# PHENIKA.net
KiCad netlist of a schematic drawn in Altium Designer
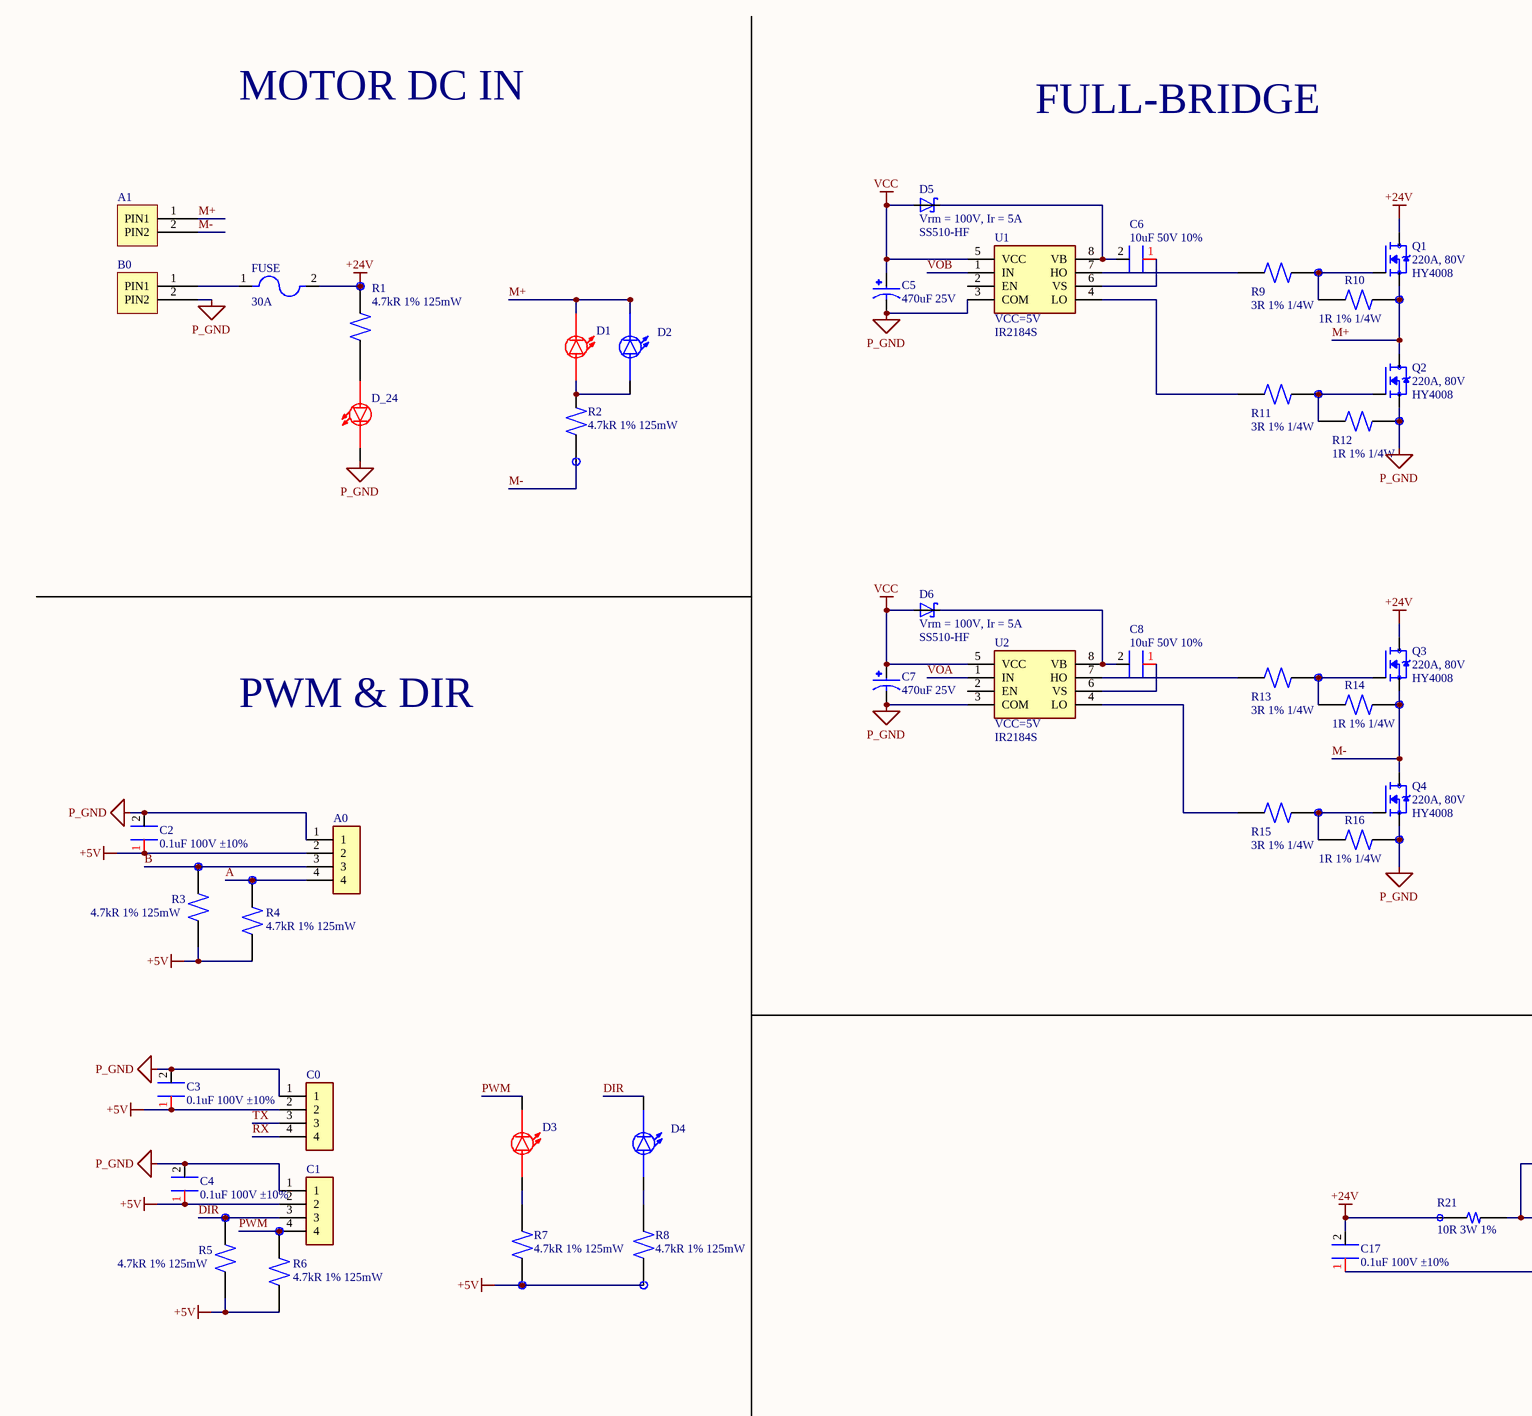
[diagram p0: PHENIKA.SchDoc, left]
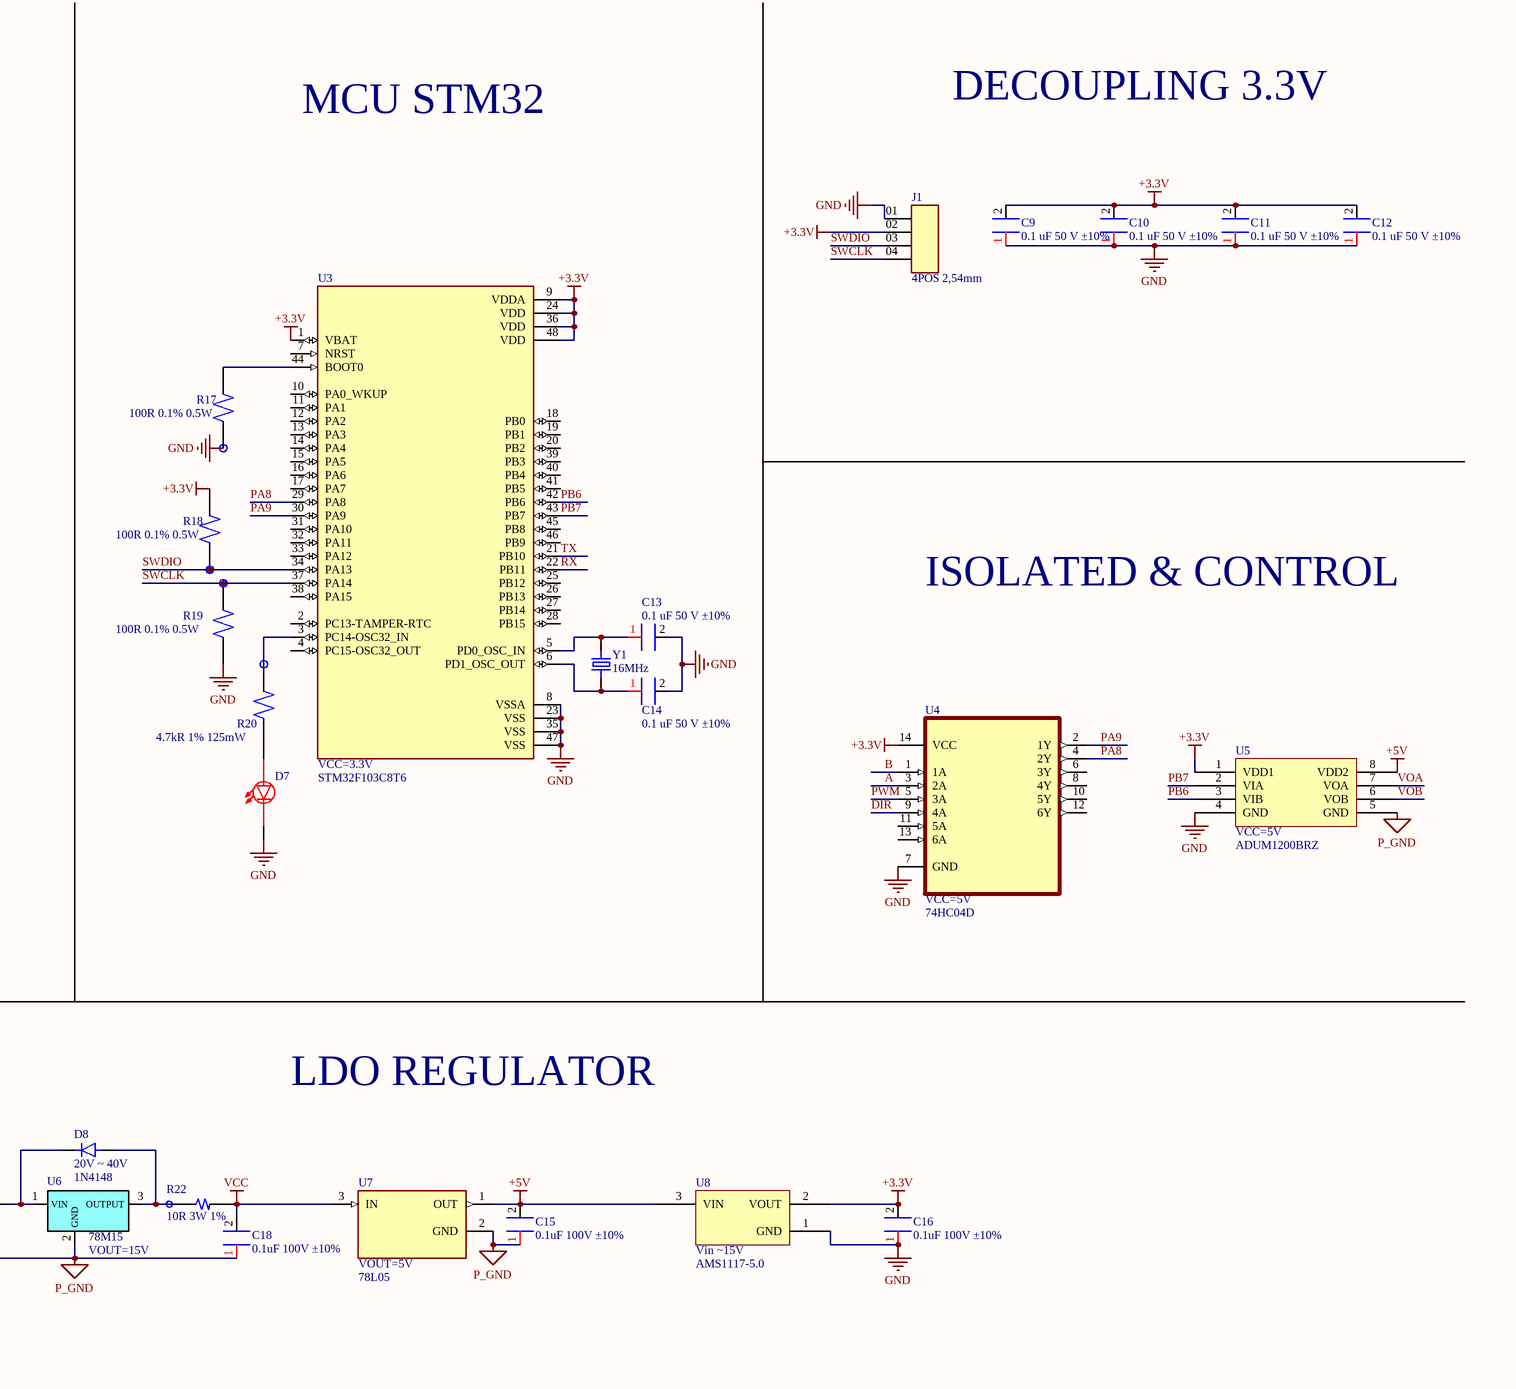
[diagram p1: PHENIKA.SchDoc, right]

(export (version "E")
  (design (tool "Eeschema 10.0.6"))
  (components
    (comp (ref "A0")
      (value "4PIN 2.5 mm")
      (footprint "HEADER-4POS_CURVED_2.54mm")
      (description "Connector Header Through Hole, Right Angle 4 position 0.079\" (2.00mm)")
      (fields
        (field (name "MANUFACTURER PART NUMBER") "S4B-PH-K-S")
        (field (name "MANUFACTURER") "JST Sales America Inc.")
      )
      (libsource (lib "MINH_REUS_LIB") (part "HEADER _4PIN;TH CURVED;2.54mm"))
    )
    (comp (ref "A1")
      (value "2PIN 2.54mm")
      (footprint "HEADER-CONN_2POS_2.54mm")
      (description "CONN HEADER VERT 2POS 2.5MM")
      (fields
        (field (name "MANUFACTURER PART NUMBER") "JST Sales America Inc.")
        (field (name "MANUFACTURER") "B2B-XH-A")
      )
      (libsource (lib "MINH_REUS_LIB") (part "HEADER 2 PIN;TH;2.54mm"))
    )
    (comp (ref "B0")
      (value "2PIN 2.54mm")
      (footprint "HEADER-CONN_2POS_2.54mm")
      (description "CONN HEADER VERT 2POS 2.5MM")
      (fields
        (field (name "MANUFACTURER PART NUMBER") "JST Sales America Inc.")
        (field (name "MANUFACTURER") "B2B-XH-A")
      )
      (libsource (lib "MINH_REUS_LIB") (part "HEADER 2 PIN;TH;2.54mm"))
    )
    (comp (ref "C0")
      (value "4PIN 2.5 mm")
      (footprint "HEADER-4POS_CURVED_2.54mm")
      (description "Connector Header Through Hole, Right Angle 4 position 0.079\" (2.00mm)")
      (fields
        (field (name "MANUFACTURER PART NUMBER") "S4B-PH-K-S")
        (field (name "MANUFACTURER") "JST Sales America Inc.")
      )
      (libsource (lib "MINH_REUS_LIB") (part "HEADER _4PIN;TH CURVED;2.54mm"))
    )
    (comp (ref "C1")
      (value "4PIN 2.5 mm")
      (footprint "HEADER-4POS_CURVED_2.54mm")
      (description "Connector Header Through Hole, Right Angle 4 position 0.079\" (2.00mm)")
      (fields
        (field (name "MANUFACTURER PART NUMBER") "S4B-PH-K-S")
        (field (name "MANUFACTURER") "JST Sales America Inc.")
      )
      (libsource (lib "MINH_REUS_LIB") (part "HEADER _4PIN;TH CURVED;2.54mm"))
    )
    (comp (ref "C2")
      (value "0.1uF 100V ±10%")
      (footprint "CAP-CER_1206 3.2x1.6x0.5mm SMD")
      (description "Multilayer Ceramic Capacitor, 0.1 uF, 100 V, ± 10%, X7R, 1206 [3216 Metric]")
      (fields
        (field (name "MANUFACTURER") "Yageo")
        (field (name "MANUFACTURER PART NUMBER") "CC1206KKX7R0BB104")
      )
      (libsource (lib "MINH_REUS_LIB") (part "CAP_CER; SMD; 0.1uF 100V ±10%;1206;"))
    )
    (comp (ref "C3")
      (value "0.1uF 100V ±10%")
      (footprint "CAP-CER_1206 3.2x1.6x0.5mm SMD")
      (description "Multilayer Ceramic Capacitor, 0.1 uF, 100 V, ± 10%, X7R, 1206 [3216 Metric]")
      (fields
        (field (name "MANUFACTURER") "Yageo")
        (field (name "MANUFACTURER PART NUMBER") "CC1206KKX7R0BB104")
      )
      (libsource (lib "MINH_REUS_LIB") (part "CAP_CER; SMD; 0.1uF 100V ±10%;1206;"))
    )
    (comp (ref "C4")
      (value "0.1uF 100V ±10%")
      (footprint "CAP-CER_1206 3.2x1.6x0.5mm SMD")
      (description "Multilayer Ceramic Capacitor, 0.1 uF, 100 V, ± 10%, X7R, 1206 [3216 Metric]")
      (fields
        (field (name "MANUFACTURER") "Yageo")
        (field (name "MANUFACTURER PART NUMBER") "CC1206KKX7R0BB104")
      )
      (libsource (lib "MINH_REUS_LIB") (part "CAP_CER; SMD; 0.1uF 100V ±10%;1206;"))
    )
    (comp (ref "C5")
      (value "470uF 25V")
      (footprint "CAP-POLARIZED TH 25V 3x5mm")
      (description "CAP_ALUM;TH;EEU-TP1E471LB;470礔 25V Aluminum Electrolytic Capacitors Radial, Can 2000 Hrs @ 125掳C")
      (fields
        (field (name "MANUFACTURER") "Panasonic")
        (field (name "MANUFACTURER PART NUMBER") "EEUTP1E471LB")
      )
      (libsource (lib "MINH_REUS_LIB") (part "CAP_ALUM;TH;470µF 25V"))
    )
    (comp (ref "C6")
      (value "10uF 50V 10%")
      (footprint "CAP-CER_0805 SMD 2.01x1.25mm")
      (description "Ceramic Capacitor, Multilayer, Ceramic, 50V, 10% +Tol, 10% -Tol, X5R, 10uF, Surface Mount, 0805")
      (fields
        (field (name "MANUFACTURER") "Murata")
        (field (name "MANUFACTURER PART NUMBER") "GRM21BR61H106KE43K")
      )
      (libsource (lib "MINH_REUS_LIB") (part "CAP_CER;10uF 50V 10%;SMD;0805"))
    )
    (comp (ref "C7")
      (value "470uF 25V")
      (footprint "CAP-POLARIZED TH 25V 3x5mm")
      (description "CAP_ALUM;TH;EEU-TP1E471LB;470礔 25V Aluminum Electrolytic Capacitors Radial, Can 2000 Hrs @ 125掳C")
      (fields
        (field (name "MANUFACTURER") "Panasonic")
        (field (name "MANUFACTURER PART NUMBER") "EEUTP1E471LB")
      )
      (libsource (lib "MINH_REUS_LIB") (part "CAP_ALUM;TH;470µF 25V"))
    )
    (comp (ref "C8")
      (value "10uF 50V 10%")
      (footprint "CAP-CER_0805 SMD 2.01x1.25mm")
      (description "Ceramic Capacitor, Multilayer, Ceramic, 50V, 10% +Tol, 10% -Tol, X5R, 10uF, Surface Mount, 0805")
      (fields
        (field (name "MANUFACTURER") "Murata")
        (field (name "MANUFACTURER PART NUMBER") "GRM21BR61H106KE43K")
      )
      (libsource (lib "MINH_REUS_LIB") (part "CAP_CER;10uF 50V 10%;SMD;0805"))
    )
    (comp (ref "C9")
      (value "0.1 uF 50 V ±10%")
      (footprint "CAP-CER_0805 SMD 2.01x1.25mm")
      (description "Multilayer Ceramic Capacitor, 0.1 uF, 50 V, ± 10%, X7R, 0805 [2012 Metric]")
      (fields
        (field (name "MANUFACTURER") "Kyocera AVX")
        (field (name "MANUFACTURER PART NUMBER") "08055C104K4T4A")
      )
      (libsource (lib "MINH_REUS_LIB") (part "CAP_CER; SMD; 0.1uF 50V ±10%;0805;"))
    )
    (comp (ref "C10")
      (value "0.1 uF 50 V ±10%")
      (footprint "CAP-CER_0805 SMD 2.01x1.25mm")
      (description "Multilayer Ceramic Capacitor, 0.1 uF, 50 V, ± 10%, X7R, 0805 [2012 Metric]")
      (fields
        (field (name "MANUFACTURER") "Kyocera AVX")
        (field (name "MANUFACTURER PART NUMBER") "08055C104K4T4A")
      )
      (libsource (lib "MINH_REUS_LIB") (part "CAP_CER; SMD; 0.1uF 50V ±10%;0805;"))
    )
    (comp (ref "C11")
      (value "0.1 uF 50 V ±10%")
      (footprint "CAP-CER_0805 SMD 2.01x1.25mm")
      (description "Multilayer Ceramic Capacitor, 0.1 uF, 50 V, ± 10%, X7R, 0805 [2012 Metric]")
      (fields
        (field (name "MANUFACTURER") "Kyocera AVX")
        (field (name "MANUFACTURER PART NUMBER") "08055C104K4T4A")
      )
      (libsource (lib "MINH_REUS_LIB") (part "CAP_CER; SMD; 0.1uF 50V ±10%;0805;"))
    )
    (comp (ref "C12")
      (value "0.1 uF 50 V ±10%")
      (footprint "CAP-CER_0805 SMD 2.01x1.25mm")
      (description "Multilayer Ceramic Capacitor, 0.1 uF, 50 V, ± 10%, X7R, 0805 [2012 Metric]")
      (fields
        (field (name "MANUFACTURER") "Kyocera AVX")
        (field (name "MANUFACTURER PART NUMBER") "08055C104K4T4A")
      )
      (libsource (lib "MINH_REUS_LIB") (part "CAP_CER; SMD; 0.1uF 50V ±10%;0805;"))
    )
    (comp (ref "C13")
      (value "0.1 uF 50 V ±10%")
      (footprint "CAP-CER_0805 SMD 2.01x1.25mm")
      (description "Multilayer Ceramic Capacitor, 0.1 uF, 50 V, ± 10%, X7R, 0805 [2012 Metric]")
      (fields
        (field (name "MANUFACTURER") "Kyocera AVX")
        (field (name "MANUFACTURER PART NUMBER") "08055C104K4T4A")
      )
      (libsource (lib "MINH_REUS_LIB") (part "CAP_CER; SMD; 0.1uF 50V ±10%;0805;"))
    )
    (comp (ref "C14")
      (value "0.1 uF 50 V ±10%")
      (footprint "CAP-CER_0805 SMD 2.01x1.25mm")
      (description "Multilayer Ceramic Capacitor, 0.1 uF, 50 V, ± 10%, X7R, 0805 [2012 Metric]")
      (fields
        (field (name "MANUFACTURER") "Kyocera AVX")
        (field (name "MANUFACTURER PART NUMBER") "08055C104K4T4A")
      )
      (libsource (lib "MINH_REUS_LIB") (part "CAP_CER; SMD; 0.1uF 50V ±10%;0805;"))
    )
    (comp (ref "C15")
      (value "0.1uF 100V ±10%")
      (footprint "CAP-CER_1206 3.2x1.6x0.5mm SMD")
      (description "Multilayer Ceramic Capacitor, 0.1 uF, 100 V, ± 10%, X7R, 1206 [3216 Metric]")
      (fields
        (field (name "MANUFACTURER") "Yageo")
        (field (name "MANUFACTURER PART NUMBER") "CC1206KKX7R0BB104")
      )
      (libsource (lib "MINH_REUS_LIB") (part "CAP_CER; SMD; 0.1uF 100V ±10%;1206;"))
    )
    (comp (ref "C16")
      (value "0.1uF 100V ±10%")
      (footprint "CAP-CER_1206 3.2x1.6x0.5mm SMD")
      (description "Multilayer Ceramic Capacitor, 0.1 uF, 100 V, ± 10%, X7R, 1206 [3216 Metric]")
      (fields
        (field (name "MANUFACTURER") "Yageo")
        (field (name "MANUFACTURER PART NUMBER") "CC1206KKX7R0BB104")
      )
      (libsource (lib "MINH_REUS_LIB") (part "CAP_CER; SMD; 0.1uF 100V ±10%;1206;"))
    )
    (comp (ref "C17")
      (value "0.1uF 100V ±10%")
      (footprint "CAP-CER_1206 3.2x1.6x0.5mm SMD")
      (description "Multilayer Ceramic Capacitor, 0.1 uF, 100 V, ± 10%, X7R, 1206 [3216 Metric]")
      (fields
        (field (name "MANUFACTURER") "Yageo")
        (field (name "MANUFACTURER PART NUMBER") "CC1206KKX7R0BB104")
      )
      (libsource (lib "MINH_REUS_LIB") (part "CAP_CER; SMD; 0.1uF 100V ±10%;1206;"))
    )
    (comp (ref "C18")
      (value "0.1uF 100V ±10%")
      (footprint "CAP-CER_1206 3.2x1.6x0.5mm SMD")
      (description "Multilayer Ceramic Capacitor, 0.1 uF, 100 V, ± 10%, X7R, 1206 [3216 Metric]")
      (fields
        (field (name "MANUFACTURER") "Yageo")
        (field (name "MANUFACTURER PART NUMBER") "CC1206KKX7R0BB104")
      )
      (libsource (lib "MINH_REUS_LIB") (part "CAP_CER; SMD; 0.1uF 100V ±10%;1206;"))
    )
    (comp (ref "D1")
      (value "XL-1608SURC-06")
      (footprint "DIODE-LED_SMD-XL-1608SURC-06 RED 1.25x1.14mm")
      (fields (field (name "MANUFACTURER") "XINGLIGHT"))
      (libsource (lib "MINH_REUS_LIB") (part "DIODE_LED;SMD;RED COLOUR"))
    )
    (comp (ref "D2")
      (value "LED BLUE")
      (footprint "DIODE-LED_SMD-LXT0805GW-TR 1.25X1.14MM")
      (description "DIODE_LED;SMD;SML-LXT0805GW-TR;Blue LED Indication - Discrete 2V 0805 _2012 Metric_")
      (fields
        (field (name "MANUFACTURER") "SML-LXT0805GW-TR")
        (field (name "MANUFACTURER PART NUMBER") "Dialight")
      )
      (libsource (lib "MINH_REUS_LIB") (part "DIODE_LED;SMD; BLUE COLOR"))
    )
    (comp (ref "D3")
      (value "XL-1608SURC-06")
      (footprint "DIODE-LED_SMD-XL-1608SURC-06 RED 1.25x1.14mm")
      (fields (field (name "MANUFACTURER") "XINGLIGHT"))
      (libsource (lib "MINH_REUS_LIB") (part "DIODE_LED;SMD;RED COLOUR"))
    )
    (comp (ref "D4")
      (value "LED BLUE")
      (footprint "DIODE-LED_SMD-LXT0805GW-TR 1.25X1.14MM")
      (description "DIODE_LED;SMD;SML-LXT0805GW-TR;Blue LED Indication - Discrete 2V 0805 _2012 Metric_")
      (fields
        (field (name "MANUFACTURER") "SML-LXT0805GW-TR")
        (field (name "MANUFACTURER PART NUMBER") "Dialight")
      )
      (libsource (lib "MINH_REUS_LIB") (part "DIODE_LED;SMD; BLUE COLOR"))
    )
    (comp (ref "D5")
      (value "Vrm = 100V, Ir = 5A")
      (footprint "DIODE_ES1J-DO214AC")
      (description "Schottky Diodes & Rectifiers DIODE SCHOTTKY 5A 100V SMA")
      (fields
        (field (name "MANUFACTURER") "Comchip Technology")
        (field (name "MANUFACTURER PART NUMBER") "SS510-HF")
        (field (name "MANUFACTURE PART NUMBER CROSS") "SS510-HF")
      )
      (libsource (lib "MINH_REUS_LIB") (part "DIODE_SCHOTTKY;Vrm = 100V, Ir =5A;SMD;SMA"))
    )
    (comp (ref "D6")
      (value "Vrm = 100V, Ir = 5A")
      (footprint "DIODE_ES1J-DO214AC")
      (description "Schottky Diodes & Rectifiers DIODE SCHOTTKY 5A 100V SMA")
      (fields
        (field (name "MANUFACTURER") "Comchip Technology")
        (field (name "MANUFACTURER PART NUMBER") "SS510-HF")
        (field (name "MANUFACTURE PART NUMBER CROSS") "SS510-HF")
      )
      (libsource (lib "MINH_REUS_LIB") (part "DIODE_SCHOTTKY;Vrm = 100V, Ir =5A;SMD;SMA"))
    )
    (comp (ref "D7")
      (value "XL-1608SURC-06")
      (footprint "DIODE-LED_SMD-XL-1608SURC-06 RED 1.25x1.14mm")
      (fields (field (name "MANUFACTURER") "XINGLIGHT"))
      (libsource (lib "MINH_REUS_LIB") (part "DIODE_LED;SMD;RED COLOUR"))
    )
    (comp (ref "D8")
      (value "20V ~ 40V")
      (footprint "DIODE-SCHOTTKY_1N4148 5x2.4x1.2mm")
      (description "DIODE SCHOTTKY; SMD; VCC 20V-->40V")
      (fields
        (field (name "MANUFACTURER PART NUMBER") "1N4148")
        (field (name "MANUFACTURER") "CHENMKO ENTERPRISE")
      )
      (libsource (lib "MINH_REUS_LIB") (part "DIODE_SCHOTTKY; SMD;"))
    )
    (comp (ref "D_24")
      (value "XL-1608SURC-06")
      (footprint "DIODE-LED_SMD-XL-1608SURC-06 RED 1.25x1.14mm")
      (fields (field (name "MANUFACTURER") "XINGLIGHT"))
      (libsource (lib "MINH_REUS_LIB") (part "DIODE_LED;SMD;RED COLOUR"))
    )
    (comp (ref "FUSE")
      (value "30A")
      (footprint "FUSE-30A-250V-DIP")
      (fields (field (name "MANUFACTURER") "BEL FUSE") (field (name "MANUFACTURER PART NUMBER") "FC-201"))
      (libsource (lib "MINH_REUS_LIB") (part "FUSE;TH;30A-250V"))
    )
    (comp (ref "J1")
      (value "4POS 2,54mm")
      (footprint "JUMP_4POS_TH_NO-BODY")
      (description "CONN HEADER VERT 4POS 2.54MM")
      (fields (field (name "MANUFACTURE PART NUMBER") "HMTSW-104-08-S-S-280"))
      (libsource (lib "MINH_REUS_LIB") (part "JUMP_4POS;TH;2.54;NO-BODY"))
    )
    (comp (ref "Q1")
      (value "220A, 80V")
      (footprint "MOSFET_N-CHANNEL_TO-263-2")
      (fields
        (field (name "MANUFACTURER") "HOOYI SEMICONDUCTOR")
        (field (name "MANUFACTURER PART NUMBER") "HY4008")
      )
      (libsource (lib "MINH_REUS_LIB") (part "MOSFET POWER;SMD; N-channel;TO-263-2;HY4008"))
    )
    (comp (ref "Q2")
      (value "220A, 80V")
      (footprint "MOSFET_N-CHANNEL_TO-263-2")
      (fields
        (field (name "MANUFACTURER") "HOOYI SEMICONDUCTOR")
        (field (name "MANUFACTURER PART NUMBER") "HY4008")
      )
      (libsource (lib "MINH_REUS_LIB") (part "MOSFET POWER;SMD; N-channel;TO-263-2;HY4008"))
    )
    (comp (ref "Q3")
      (value "220A, 80V")
      (footprint "MOSFET_N-CHANNEL_TO-263-2")
      (fields
        (field (name "MANUFACTURER") "HOOYI SEMICONDUCTOR")
        (field (name "MANUFACTURER PART NUMBER") "HY4008")
      )
      (libsource (lib "MINH_REUS_LIB") (part "MOSFET POWER;SMD; N-channel;TO-263-2;HY4008"))
    )
    (comp (ref "Q4")
      (value "220A, 80V")
      (footprint "MOSFET_N-CHANNEL_TO-263-2")
      (fields
        (field (name "MANUFACTURER") "HOOYI SEMICONDUCTOR")
        (field (name "MANUFACTURER PART NUMBER") "HY4008")
      )
      (libsource (lib "MINH_REUS_LIB") (part "MOSFET POWER;SMD; N-channel;TO-263-2;HY4008"))
    )
    (comp (ref "R1")
      (value "4.7kR 1% 125mW")
      (footprint "RES_0805 2x1.25mm")
      (fields
        (field (name "MANUFACTURER") "UNI-ROYAL(Uniroyal Elec)")
        (field (name "MANUFACTURER PART NUMBER") "0805W8F4701T5E")
      )
      (libsource (lib "MINH_REUS_LIB") (part "RES;SMD;4.7kR 0.1% 125mW ;0805;"))
    )
    (comp (ref "R2")
      (value "4.7kR 1% 125mW")
      (footprint "RES_0805 2x1.25mm")
      (fields
        (field (name "MANUFACTURER") "UNI-ROYAL(Uniroyal Elec)")
        (field (name "MANUFACTURER PART NUMBER") "0805W8F4701T5E")
      )
      (libsource (lib "MINH_REUS_LIB") (part "RES;SMD;4.7kR 0.1% 125mW ;0805;"))
    )
    (comp (ref "R3")
      (value "4.7kR 1% 125mW")
      (footprint "RES_0805 2x1.25mm")
      (fields
        (field (name "MANUFACTURER") "UNI-ROYAL(Uniroyal Elec)")
        (field (name "MANUFACTURER PART NUMBER") "0805W8F4701T5E")
      )
      (libsource (lib "MINH_REUS_LIB") (part "RES;SMD;4.7kR 0.1% 125mW ;0805;"))
    )
    (comp (ref "R4")
      (value "4.7kR 1% 125mW")
      (footprint "RES_0805 2x1.25mm")
      (fields
        (field (name "MANUFACTURER") "UNI-ROYAL(Uniroyal Elec)")
        (field (name "MANUFACTURER PART NUMBER") "0805W8F4701T5E")
      )
      (libsource (lib "MINH_REUS_LIB") (part "RES;SMD;4.7kR 0.1% 125mW ;0805;"))
    )
    (comp (ref "R5")
      (value "4.7kR 1% 125mW")
      (footprint "RES_0805 2x1.25mm")
      (fields
        (field (name "MANUFACTURER") "UNI-ROYAL(Uniroyal Elec)")
        (field (name "MANUFACTURER PART NUMBER") "0805W8F4701T5E")
      )
      (libsource (lib "MINH_REUS_LIB") (part "RES;SMD;4.7kR 0.1% 125mW ;0805;"))
    )
    (comp (ref "R6")
      (value "4.7kR 1% 125mW")
      (footprint "RES_0805 2x1.25mm")
      (fields
        (field (name "MANUFACTURER") "UNI-ROYAL(Uniroyal Elec)")
        (field (name "MANUFACTURER PART NUMBER") "0805W8F4701T5E")
      )
      (libsource (lib "MINH_REUS_LIB") (part "RES;SMD;4.7kR 0.1% 125mW ;0805;"))
    )
    (comp (ref "R7")
      (value "4.7kR 1% 125mW")
      (footprint "RES_0805 2x1.25mm")
      (fields
        (field (name "MANUFACTURER") "UNI-ROYAL(Uniroyal Elec)")
        (field (name "MANUFACTURER PART NUMBER") "0805W8F4701T5E")
      )
      (libsource (lib "MINH_REUS_LIB") (part "RES;SMD;4.7kR 0.1% 125mW ;0805;"))
    )
    (comp (ref "R8")
      (value "4.7kR 1% 125mW")
      (footprint "RES_0805 2x1.25mm")
      (fields
        (field (name "MANUFACTURER") "UNI-ROYAL(Uniroyal Elec)")
        (field (name "MANUFACTURER PART NUMBER") "0805W8F4701T5E")
      )
      (libsource (lib "MINH_REUS_LIB") (part "RES;SMD;4.7kR 0.1% 125mW ;0805;"))
    )
    (comp (ref "R9")
      (value "3R 1% 1/4W")
      (footprint "RES_0805 2x1.25mm")
      (description "RES;SMD;0R 1%;0805; Thick Film Resistors - SMD 1/4watt 0ohms")
      (fields
        (field (name "MANUFACTURER PART NUMBER") "CRCW12060000Z0EA")
        (field (name "MANUFACTURER") "Vishay / Dale")
      )
      (libsource (lib "MINH_REUS_LIB") (part "RES;SMD;0R 1%;0805"))
    )
    (comp (ref "R10")
      (value "1R 1% 1/4W")
      (footprint "RES_0805 2x1.25mm")
      (description "RES;SMD;0R 1%;0805; Thick Film Resistors - SMD 1/4watt 0ohms")
      (fields
        (field (name "MANUFACTURER PART NUMBER") "CRCW12060000Z0EA")
        (field (name "MANUFACTURER") "Vishay / Dale")
      )
      (libsource (lib "MINH_REUS_LIB") (part "RES;SMD;0R 1%;0805"))
    )
    (comp (ref "R11")
      (value "3R 1% 1/4W")
      (footprint "RES_0805 2x1.25mm")
      (description "RES;SMD;0R 1%;0805; Thick Film Resistors - SMD 1/4watt 0ohms")
      (fields
        (field (name "MANUFACTURER PART NUMBER") "CRCW12060000Z0EA")
        (field (name "MANUFACTURER") "Vishay / Dale")
      )
      (libsource (lib "MINH_REUS_LIB") (part "RES;SMD;0R 1%;0805"))
    )
    (comp (ref "R12")
      (value "1R 1% 1/4W")
      (footprint "RES_0805 2x1.25mm")
      (description "RES;SMD;0R 1%;0805; Thick Film Resistors - SMD 1/4watt 0ohms")
      (fields
        (field (name "MANUFACTURER PART NUMBER") "CRCW12060000Z0EA")
        (field (name "MANUFACTURER") "Vishay / Dale")
      )
      (libsource (lib "MINH_REUS_LIB") (part "RES;SMD;0R 1%;0805"))
    )
    (comp (ref "R13")
      (value "3R 1% 1/4W")
      (footprint "RES_0805 2x1.25mm")
      (description "RES;SMD;0R 1%;0805; Thick Film Resistors - SMD 1/4watt 0ohms")
      (fields
        (field (name "MANUFACTURER PART NUMBER") "CRCW12060000Z0EA")
        (field (name "MANUFACTURER") "Vishay / Dale")
      )
      (libsource (lib "MINH_REUS_LIB") (part "RES;SMD;0R 1%;0805"))
    )
    (comp (ref "R14")
      (value "1R 1% 1/4W")
      (footprint "RES_0805 2x1.25mm")
      (description "RES;SMD;0R 1%;0805; Thick Film Resistors - SMD 1/4watt 0ohms")
      (fields
        (field (name "MANUFACTURER PART NUMBER") "CRCW12060000Z0EA")
        (field (name "MANUFACTURER") "Vishay / Dale")
      )
      (libsource (lib "MINH_REUS_LIB") (part "RES;SMD;0R 1%;0805"))
    )
    (comp (ref "R15")
      (value "3R 1% 1/4W")
      (footprint "RES_0805 2x1.25mm")
      (description "RES;SMD;0R 1%;0805; Thick Film Resistors - SMD 1/4watt 0ohms")
      (fields
        (field (name "MANUFACTURER PART NUMBER") "CRCW12060000Z0EA")
        (field (name "MANUFACTURER") "Vishay / Dale")
      )
      (libsource (lib "MINH_REUS_LIB") (part "RES;SMD;0R 1%;0805"))
    )
    (comp (ref "R16")
      (value "1R 1% 1/4W")
      (footprint "RES_0805 2x1.25mm")
      (description "RES;SMD;0R 1%;0805; Thick Film Resistors - SMD 1/4watt 0ohms")
      (fields
        (field (name "MANUFACTURER PART NUMBER") "CRCW12060000Z0EA")
        (field (name "MANUFACTURER") "Vishay / Dale")
      )
      (libsource (lib "MINH_REUS_LIB") (part "RES;SMD;0R 1%;0805"))
    )
    (comp (ref "R17")
      (value "100R 0.1% 0.5W")
      (footprint "RES_0805 2x1.25mm")
      (description "Thick Film Resistors 0805 120ohms 0.5W 0.5% AEC-Q200")
      (fields
        (field (name "MANUFACTURER PART NUMBER") "ERJ-P06D1200V")
        (field (name "MANUFACTURER") "Panasonic")
      )
      (libsource (lib "MINH_REUS_LIB") (part "RES; SMD; 120R 0.1% 0.5W;0805"))
    )
    (comp (ref "R18")
      (value "100R 0.1% 0.5W")
      (footprint "RES_0805 2x1.25mm")
      (description "Thick Film Resistors 0805 120ohms 0.5W 0.5% AEC-Q200")
      (fields
        (field (name "MANUFACTURER PART NUMBER") "ERJ-P06D1200V")
        (field (name "MANUFACTURER") "Panasonic")
      )
      (libsource (lib "MINH_REUS_LIB") (part "RES; SMD; 120R 0.1% 0.5W;0805"))
    )
    (comp (ref "R19")
      (value "100R 0.1% 0.5W")
      (footprint "RES_0805 2x1.25mm")
      (description "Thick Film Resistors 0805 120ohms 0.5W 0.5% AEC-Q200")
      (fields
        (field (name "MANUFACTURER PART NUMBER") "ERJ-P06D1200V")
        (field (name "MANUFACTURER") "Panasonic")
      )
      (libsource (lib "MINH_REUS_LIB") (part "RES; SMD; 120R 0.1% 0.5W;0805"))
    )
    (comp (ref "R20")
      (value "4.7kR 1% 125mW")
      (footprint "RES_0805 2x1.25mm")
      (fields
        (field (name "MANUFACTURER") "UNI-ROYAL(Uniroyal Elec)")
        (field (name "MANUFACTURER PART NUMBER") "0805W8F4701T5E")
      )
      (libsource (lib "MINH_REUS_LIB") (part "RES;SMD;4.7kR 0.1% 125mW ;0805;"))
    )
    (comp (ref "R21")
      (value "10R 3W 1%")
      (footprint "RES_2512 SMD 6.3x2.15x0.7mm")
      (description "RES;SMD;12R 3W 1%; 2512")
      (fields
        (field (name "MANUFACTURER") "TE Connectivity")
        (field (name "MANUFACTURER PART NUMBER") "2176231-3")
      )
      (libsource (lib "MINH_REUS_LIB") (part "RES;SMD;12R 3W 1%;2512"))
    )
    (comp (ref "R22")
      (value "10R 3W 1%")
      (footprint "RES_2512 SMD 6.3x2.15x0.7mm")
      (description "RES;SMD;12R 3W 1%; 2512")
      (fields
        (field (name "MANUFACTURER") "TE Connectivity")
        (field (name "MANUFACTURER PART NUMBER") "2176231-3")
      )
      (libsource (lib "MINH_REUS_LIB") (part "RES;SMD;12R 3W 1%;2512"))
    )
    (comp (ref "U1")
      (value "VCC=5V")
      (footprint "IC_OP-AMP_MAX4213_SOIC8")
      (description "Half-Bridge Gate Driver IC Non-Inverting 8-SOIC")
      (fields
        (field (name "MANUFACTURER") "Infineon Technologies")
        (field (name "MANUFACTURER PART NUMBER") "IR2184S")
      )
      (libsource (lib "MINH_REUS_LIB") (part "IC_HALF-BRIDGE_DRIVER;SMD;SOIC-8;IR2184S"))
    )
    (comp (ref "U2")
      (value "VCC=5V")
      (footprint "IC_OP-AMP_MAX4213_SOIC8")
      (description "Half-Bridge Gate Driver IC Non-Inverting 8-SOIC")
      (fields
        (field (name "MANUFACTURER") "Infineon Technologies")
        (field (name "MANUFACTURER PART NUMBER") "IR2184S")
      )
      (libsource (lib "MINH_REUS_LIB") (part "IC_HALF-BRIDGE_DRIVER;SMD;SOIC-8;IR2184S"))
    )
    (comp (ref "U3")
      (value "VCC=3.3V")
      (footprint "MCU_STM32F103C8T6_LQFP-48")
      (description "ARM® Cortex®-M3 STM32F1 Microcontroller IC 32-Bit Single-Core 72MHz 64KB (64K x 8) FLASH")
      (fields
        (field (name "MANUFACTURER PART NUMBER") "STM32F103C8T6")
        (field (name "MANUFACTURER") "STMicroelectronics")
      )
      (libsource (lib "MINH_REUS_LIB") (part "MCU_STM32F103C8T6;SMD;LQFP48"))
    )
    (comp (ref "U4")
      (value "VCC=5V")
      (footprint "IC_74HC04D_SOIC-14")
      (description "IC INVERTER 6CH 1-INP 14SOIC Inverter IC 6 Channel 14-SOIC")
      (fields
        (field (name "MANUFACTURER") "Toshiba Semiconductor and Storage")
        (field (name "MANUFACTURER PART NUMBER") "74HC04D")
      )
      (libsource (lib "MINH_REUS_LIB") (part "IC_INVERTER_6CH;SMD;SOP14;74HC04D"))
    )
    (comp (ref "U5")
      (value "VCC=5V")
      (footprint "IC-HALL-SENSOR_ACS712-SOIC-8")
      (description "Digital Isolators DUAL-CHANNEL DIGITAL ISOLATORS")
      (fields
        (field (name "MANUFACTURER") "Analog Devices")
        (field (name "MANUFACTURER PART NUMBER") "ADUM1200BRZ")
      )
      (libsource (lib "MINH_REUS_LIB") (part "IC_ISOLATOR;SMD; SOIC-8;"))
    )
    (comp (ref "U6")
      (value "VOUT=15V")
      (footprint "IC_LDO_TO-252_78M15")
      (fields
        (field (name "MANUFACTURER PART NUMBER") "78M15")
        (field (name "MANUFACTURE PART NUMBER CROSS") "78M15")
        (field (name "MANUFACTURER") "GOODWORK")
      )
      (libsource (lib "MINH_REUS_LIB") (part "IC POWER_SMD;78M15;TO252"))
    )
    (comp (ref "U7")
      (value "VOUT=5V")
      (footprint "IC_HT7233-SOT89")
      (description "PMIC - Spannungsregler - Linear Positiv Fest 1 Ausgang 100mA SOT-89")
      (fields (field (name "MANUFACTURER") "UMW") (field (name "MANUFACTURER PART NUMBER") "78L05"))
      (libsource (lib "MINH_REUS_LIB") (part "IC_LDO;SMD;SOT89;78L05"))
    )
    (comp (ref "U8")
      (value "Vin ~15V")
      (footprint "IC_HT7533-3_SOT89")
      (description "IC LDO REG 5V 1A SOT223Linear Voltage Regulator IC Positive Fixed 1 Output 1A SOT-223s")
      (fields (field (name "MANUFACTURER") "AMS") (field (name "MANUFACTURER PART NUMBER") "AMS1117-5.0"))
      (libsource (lib "MINH_REUS_LIB") (part "IC_LDO;5V 1A;SMD SOT223"))
    )
    (comp (ref "Y1")
      (value "16MHz")
      (footprint "OSCILATOR-4.9152 MHz")
      (description "Crystals CRYSTAL 16MHZ 18PF T/H")
      (fields
        (field (name "MANUFACTURER") "ABRACON")
        (field (name "MANUFACTURER PART NUMBER") "ABL-16.000MHz-B4Y")
      )
      (libsource (lib "MINH_REUS_LIB") (part "OSCILLATOR;16MHz; ±20ppm;ABL-16MHZ-B4Y"))
    )
  )
  (nets
    (net (code "1") (name "+3.3V") (class "Default")
      (node (ref "C10") (pin "2") (pintype "passive"))
      (node (ref "C11") (pin "2") (pintype "passive"))
      (node (ref "C12") (pin "2") (pintype "passive"))
      (node (ref "C16") (pin "2") (pintype "passive"))
      (node (ref "C9") (pin "2") (pintype "passive"))
      (node (ref "J1") (pin "02") (pinfunction "02_02") (pintype "passive"))
      (node (ref "R18") (pin "2") (pinfunction "2_2") (pintype "passive"))
      (node (ref "U3") (pin "1") (pinfunction "VBAT_1") (pintype "bidirectional"))
      (node (ref "U3") (pin "24") (pinfunction "VDD_24") (pintype "power_in"))
      (node (ref "U3") (pin "36") (pinfunction "VDD_36") (pintype "power_in"))
      (node (ref "U3") (pin "48") (pinfunction "VDD_48") (pintype "power_in"))
      (node (ref "U3") (pin "9") (pinfunction "VDDA_9") (pintype "power_in"))
      (node (ref "U4") (pin "14") (pinfunction "VCC_14") (pintype "power_in"))
      (node (ref "U5") (pin "1") (pinfunction "VDD1_1") (pintype "passive"))
      (node (ref "U8") (pin "2") (pinfunction "VOUT_2") (pintype "passive"))
    )
    (net (code "2") (name "+5V") (class "Default")
      (node (ref "A0") (pin "2") (pinfunction "2_2") (pintype "passive"))
      (node (ref "C0") (pin "2") (pinfunction "2_2") (pintype "passive"))
      (node (ref "C1") (pin "2") (pinfunction "2_2") (pintype "passive"))
      (node (ref "C15") (pin "2") (pintype "passive"))
      (node (ref "C2") (pin "1") (pintype "passive"))
      (node (ref "C3") (pin "1") (pintype "passive"))
      (node (ref "C4") (pin "1") (pintype "passive"))
      (node (ref "R3") (pin "2") (pinfunction "2_2") (pintype "passive"))
      (node (ref "R4") (pin "2") (pinfunction "2_2") (pintype "passive"))
      (node (ref "R5") (pin "2") (pinfunction "2_2") (pintype "passive"))
      (node (ref "R6") (pin "2") (pinfunction "2_2") (pintype "passive"))
      (node (ref "R7") (pin "1") (pinfunction "1_1") (pintype "passive"))
      (node (ref "R8") (pin "1") (pinfunction "1_1") (pintype "passive"))
      (node (ref "U5") (pin "8") (pinfunction "VDD2_8") (pintype "passive"))
      (node (ref "U7") (pin "1") (pinfunction "OUT_1") (pintype "output"))
      (node (ref "U8") (pin "3") (pinfunction "VIN_3") (pintype "passive"))
    )
    (net (code "3") (name "+24V") (class "Default")
      (node (ref "C17") (pin "2") (pintype "passive"))
      (node (ref "FUSE") (pin "2") (pinfunction "2_2") (pintype "passive"))
      (node (ref "Q1") (pin "3") (pinfunction "D_3") (pintype "passive"))
      (node (ref "Q3") (pin "3") (pinfunction "D_3") (pintype "passive"))
      (node (ref "R1") (pin "1") (pinfunction "1_1") (pintype "passive"))
      (node (ref "R21") (pin "1") (pinfunction "1_1") (pintype "passive"))
    )
    (net (code "4") (name "/A") (class "Default")
      (node (ref "A0") (pin "4") (pinfunction "4_4") (pintype "passive"))
      (node (ref "R4") (pin "1") (pinfunction "1_1") (pintype "passive"))
      (node (ref "U4") (pin "3") (pinfunction "2A_3") (pintype "input"))
    )
    (net (code "5") (name "/B") (class "Default")
      (node (ref "A0") (pin "3") (pinfunction "3_3") (pintype "passive"))
      (node (ref "R3") (pin "1") (pinfunction "1_1") (pintype "passive"))
      (node (ref "U4") (pin "1") (pinfunction "1A_1") (pintype "input"))
    )
    (net (code "6") (name "/DIR") (class "Default")
      (node (ref "C1") (pin "3") (pinfunction "3_3") (pintype "passive"))
      (node (ref "D4") (pin "C") (pinfunction "C_C") (pintype "passive"))
      (node (ref "R5") (pin "1") (pinfunction "1_1") (pintype "passive"))
      (node (ref "U4") (pin "9") (pinfunction "4A_9") (pintype "input"))
    )
    (net (code "7") (name "/M+") (class "Default")
      (node (ref "A1") (pin "1") (pinfunction "PIN1_1") (pintype "passive"))
      (node (ref "D1") (pin "C") (pinfunction "C_C") (pintype "passive"))
      (node (ref "D2") (pin "C") (pinfunction "C_C") (pintype "passive"))
      (node (ref "Q1") (pin "2") (pinfunction "S_2") (pintype "passive"))
      (node (ref "Q2") (pin "3") (pinfunction "D_3") (pintype "passive"))
      (node (ref "R10") (pin "1") (pinfunction "1_1") (pintype "passive"))
    )
    (net (code "8") (name "/M-") (class "Default")
      (node (ref "A1") (pin "2") (pinfunction "PIN2_2") (pintype "passive"))
      (node (ref "Q3") (pin "2") (pinfunction "S_2") (pintype "passive"))
      (node (ref "Q4") (pin "3") (pinfunction "D_3") (pintype "passive"))
      (node (ref "R14") (pin "1") (pinfunction "1_1") (pintype "passive"))
      (node (ref "R2") (pin "1") (pinfunction "1_1") (pintype "passive"))
    )
    (net (code "9") (name "/PA8") (class "Default")
      (node (ref "U3") (pin "29") (pinfunction "PA8_29") (pintype "bidirectional"))
      (node (ref "U4") (pin "4") (pinfunction "2Y_4") (pintype "output"))
    )
    (net (code "10") (name "/PA9") (class "Default")
      (node (ref "U3") (pin "30") (pinfunction "PA9_30") (pintype "bidirectional"))
      (node (ref "U4") (pin "2") (pinfunction "1Y_2") (pintype "output"))
    )
    (net (code "11") (name "/PB6") (class "Default")
      (node (ref "U3") (pin "42") (pinfunction "PB6_42") (pintype "bidirectional"))
      (node (ref "U5") (pin "3") (pinfunction "VIB_3") (pintype "passive"))
    )
    (net (code "12") (name "/PB7") (class "Default")
      (node (ref "U3") (pin "43") (pinfunction "PB7_43") (pintype "bidirectional"))
      (node (ref "U5") (pin "2") (pinfunction "VIA_2") (pintype "passive"))
    )
    (net (code "13") (name "/PWM") (class "Default")
      (node (ref "C1") (pin "4") (pinfunction "4_4") (pintype "passive"))
      (node (ref "D3") (pin "C") (pinfunction "C_C") (pintype "passive"))
      (node (ref "R6") (pin "1") (pinfunction "1_1") (pintype "passive"))
      (node (ref "U4") (pin "5") (pinfunction "3A_5") (pintype "input"))
    )
    (net (code "14") (name "/RX") (class "Default")
      (node (ref "C0") (pin "4") (pinfunction "4_4") (pintype "passive"))
      (node (ref "U3") (pin "22") (pinfunction "PB11_22") (pintype "bidirectional"))
    )
    (net (code "15") (name "/SWCLK") (class "Default")
      (node (ref "J1") (pin "04") (pinfunction "04_04") (pintype "passive"))
      (node (ref "R19") (pin "1") (pinfunction "1_1") (pintype "passive"))
      (node (ref "U3") (pin "37") (pinfunction "PA14_37") (pintype "bidirectional"))
    )
    (net (code "16") (name "/SWDIO") (class "Default")
      (node (ref "J1") (pin "03") (pinfunction "03_03") (pintype "passive"))
      (node (ref "R18") (pin "1") (pinfunction "1_1") (pintype "passive"))
      (node (ref "U3") (pin "34") (pinfunction "PA13_34") (pintype "bidirectional"))
    )
    (net (code "17") (name "/TX") (class "Default")
      (node (ref "C0") (pin "3") (pinfunction "3_3") (pintype "passive"))
      (node (ref "U3") (pin "21") (pinfunction "PB10_21") (pintype "bidirectional"))
    )
    (net (code "18") (name "/VOA") (class "Default")
      (node (ref "U2") (pin "1") (pinfunction "IN_1") (pintype "passive"))
      (node (ref "U5") (pin "7") (pinfunction "VOA_7") (pintype "passive"))
    )
    (net (code "19") (name "/VOB") (class "Default")
      (node (ref "U1") (pin "1") (pinfunction "IN_1") (pintype "passive"))
      (node (ref "U5") (pin "6") (pinfunction "VOB_6") (pintype "passive"))
    )
    (net (code "20") (name "GND") (class "Default")
      (node (ref "C10") (pin "1") (pintype "passive"))
      (node (ref "C11") (pin "1") (pintype "passive"))
      (node (ref "C12") (pin "1") (pintype "passive"))
      (node (ref "C13") (pin "2") (pintype "passive"))
      (node (ref "C14") (pin "2") (pintype "passive"))
      (node (ref "C16") (pin "1") (pintype "passive"))
      (node (ref "C9") (pin "1") (pintype "passive"))
      (node (ref "D7") (pin "C") (pinfunction "C_C") (pintype "passive"))
      (node (ref "J1") (pin "01") (pinfunction "01_01") (pintype "passive"))
      (node (ref "R17") (pin "1") (pinfunction "1_1") (pintype "passive"))
      (node (ref "R19") (pin "2") (pinfunction "2_2") (pintype "passive"))
      (node (ref "U3") (pin "23") (pinfunction "VSS_23") (pintype "power_in"))
      (node (ref "U3") (pin "35") (pinfunction "VSS_35") (pintype "power_in"))
      (node (ref "U3") (pin "47") (pinfunction "VSS_47") (pintype "power_in"))
      (node (ref "U3") (pin "8") (pinfunction "VSSA_8") (pintype "power_in"))
      (node (ref "U4") (pin "7") (pinfunction "GND_7") (pintype "passive"))
      (node (ref "U5") (pin "4") (pinfunction "GND_4") (pintype "passive"))
      (node (ref "U8") (pin "1") (pinfunction "GND_1") (pintype "passive"))
    )
    (net (code "21") (name "Net-(B0-PIN1)") (class "Default")
      (node (ref "B0") (pin "1") (pinfunction "PIN1_1") (pintype "passive"))
      (node (ref "FUSE") (pin "1") (pinfunction "1_1") (pintype "passive"))
    )
    (net (code "22") (name "Net-(D1-PadA)") (class "Default")
      (node (ref "D1") (pin "A") (pinfunction "A_A") (pintype "passive"))
      (node (ref "D2") (pin "A") (pinfunction "A_A") (pintype "passive"))
      (node (ref "R2") (pin "2") (pinfunction "2_2") (pintype "passive"))
    )
    (net (code "23") (name "Net-(D3-PadA)") (class "Default")
      (node (ref "D3") (pin "A") (pinfunction "A_A") (pintype "passive"))
      (node (ref "R7") (pin "2") (pinfunction "2_2") (pintype "passive"))
    )
    (net (code "24") (name "Net-(D4-PadA)") (class "Default")
      (node (ref "D4") (pin "A") (pinfunction "A_A") (pintype "passive"))
      (node (ref "R8") (pin "2") (pinfunction "2_2") (pintype "passive"))
    )
    (net (code "25") (name "Net-(D7-PadA)") (class "Default")
      (node (ref "D7") (pin "A") (pinfunction "A_A") (pintype "passive"))
      (node (ref "R20") (pin "2") (pinfunction "2_2") (pintype "passive"))
    )
    (net (code "26") (name "Net-(D_24-PadA)") (class "Default")
      (node (ref "D_24") (pin "A") (pinfunction "A_A") (pintype "passive"))
      (node (ref "R1") (pin "2") (pinfunction "2_2") (pintype "passive"))
    )
    (net (code "27") (name "Net-(Q1-G)") (class "Default")
      (node (ref "Q1") (pin "1") (pinfunction "G_1") (pintype "passive"))
      (node (ref "R10") (pin "2") (pinfunction "2_2") (pintype "passive"))
      (node (ref "R9") (pin "1") (pinfunction "1_1") (pintype "passive"))
    )
    (net (code "28") (name "Net-(Q2-G)") (class "Default")
      (node (ref "Q2") (pin "1") (pinfunction "G_1") (pintype "passive"))
      (node (ref "R11") (pin "1") (pinfunction "1_1") (pintype "passive"))
      (node (ref "R12") (pin "2") (pinfunction "2_2") (pintype "passive"))
    )
    (net (code "29") (name "Net-(Q3-G)") (class "Default")
      (node (ref "Q3") (pin "1") (pinfunction "G_1") (pintype "passive"))
      (node (ref "R13") (pin "1") (pinfunction "1_1") (pintype "passive"))
      (node (ref "R14") (pin "2") (pinfunction "2_2") (pintype "passive"))
    )
    (net (code "30") (name "Net-(Q4-G)") (class "Default")
      (node (ref "Q4") (pin "1") (pinfunction "G_1") (pintype "passive"))
      (node (ref "R15") (pin "1") (pinfunction "1_1") (pintype "passive"))
      (node (ref "R16") (pin "2") (pinfunction "2_2") (pintype "passive"))
    )
    (net (code "31") (name "Net-(U1-HO)") (class "Default")
      (node (ref "R9") (pin "2") (pinfunction "2_2") (pintype "passive"))
      (node (ref "U1") (pin "7") (pinfunction "HO_7") (pintype "passive"))
    )
    (net (code "32") (name "Net-(U1-LO)") (class "Default")
      (node (ref "R11") (pin "2") (pinfunction "2_2") (pintype "passive"))
      (node (ref "U1") (pin "4") (pinfunction "LO_4") (pintype "passive"))
    )
    (net (code "33") (name "Net-(U1-VB)") (class "Default")
      (node (ref "C6") (pin "2") (pintype "passive"))
      (node (ref "D5") (pin "C") (pinfunction "C_C") (pintype "passive"))
      (node (ref "U1") (pin "8") (pinfunction "VB_8") (pintype "passive"))
    )
    (net (code "34") (name "Net-(U1-VS)") (class "Default")
      (node (ref "C6") (pin "1") (pintype "passive"))
      (node (ref "U1") (pin "6") (pinfunction "VS_6") (pintype "passive"))
    )
    (net (code "35") (name "Net-(U2-HO)") (class "Default")
      (node (ref "R13") (pin "2") (pinfunction "2_2") (pintype "passive"))
      (node (ref "U2") (pin "7") (pinfunction "HO_7") (pintype "passive"))
    )
    (net (code "36") (name "Net-(U2-LO)") (class "Default")
      (node (ref "R15") (pin "2") (pinfunction "2_2") (pintype "passive"))
      (node (ref "U2") (pin "4") (pinfunction "LO_4") (pintype "passive"))
    )
    (net (code "37") (name "Net-(U2-VB)") (class "Default")
      (node (ref "C8") (pin "2") (pintype "passive"))
      (node (ref "D6") (pin "C") (pinfunction "C_C") (pintype "passive"))
      (node (ref "U2") (pin "8") (pinfunction "VB_8") (pintype "passive"))
    )
    (net (code "38") (name "Net-(U2-VS)") (class "Default")
      (node (ref "C8") (pin "1") (pintype "passive"))
      (node (ref "U2") (pin "6") (pinfunction "VS_6") (pintype "passive"))
    )
    (net (code "39") (name "Net-(U3-BOOT0)") (class "Default")
      (node (ref "R17") (pin "2") (pinfunction "2_2") (pintype "passive"))
      (node (ref "U3") (pin "44") (pinfunction "BOOT0_44") (pintype "input"))
    )
    (net (code "40") (name "Net-(U3-PC14-OSC32_IN)") (class "Default")
      (node (ref "R20") (pin "1") (pinfunction "1_1") (pintype "passive"))
      (node (ref "U3") (pin "3") (pinfunction "PC14-OSC32_IN_3") (pintype "bidirectional"))
    )
    (net (code "41") (name "Net-(U3-PD0_OSC_IN)") (class "Default")
      (node (ref "C13") (pin "1") (pintype "passive"))
      (node (ref "U3") (pin "5") (pinfunction "PD0_OSC_IN_5") (pintype "bidirectional"))
      (node (ref "Y1") (pin "2") (pinfunction "2_2") (pintype "passive"))
    )
    (net (code "42") (name "Net-(U3-PD1_OSC_OUT)") (class "Default")
      (node (ref "C14") (pin "1") (pintype "passive"))
      (node (ref "U3") (pin "6") (pinfunction "PD1_OSC_OUT_6") (pintype "bidirectional"))
      (node (ref "Y1") (pin "1") (pinfunction "1_1") (pintype "passive"))
    )
    (net (code "43") (name "Net-(U6-OUTPUT)") (class "Default")
      (node (ref "D8") (pin "A") (pinfunction "A_A") (pintype "passive"))
      (node (ref "R22") (pin "1") (pinfunction "1_1") (pintype "passive"))
      (node (ref "U6") (pin "3") (pinfunction "OUTPUT_3") (pintype "passive"))
    )
    (net (code "44") (name "Net-(U6-VIN)") (class "Default")
      (node (ref "D8") (pin "K") (pinfunction "K_K") (pintype "passive"))
      (node (ref "R21") (pin "2") (pinfunction "2_2") (pintype "passive"))
      (node (ref "U6") (pin "1") (pinfunction "VIN_1") (pintype "passive"))
    )
    (net (code "45") (name "P_GND") (class "Default")
      (node (ref "A0") (pin "1") (pinfunction "1_1") (pintype "passive"))
      (node (ref "B0") (pin "2") (pinfunction "PIN2_2") (pintype "passive"))
      (node (ref "C0") (pin "1") (pinfunction "1_1") (pintype "passive"))
      (node (ref "C1") (pin "1") (pinfunction "1_1") (pintype "passive"))
      (node (ref "C15") (pin "1") (pintype "passive"))
      (node (ref "C17") (pin "1") (pintype "passive"))
      (node (ref "C18") (pin "1") (pintype "passive"))
      (node (ref "C2") (pin "2") (pintype "passive"))
      (node (ref "C3") (pin "2") (pintype "passive"))
      (node (ref "C4") (pin "2") (pintype "passive"))
      (node (ref "C5") (pin "2") (pinfunction "2_2") (pintype "passive"))
      (node (ref "C7") (pin "2") (pinfunction "2_2") (pintype "passive"))
      (node (ref "D_24") (pin "C") (pinfunction "C_C") (pintype "passive"))
      (node (ref "Q2") (pin "2") (pinfunction "S_2") (pintype "passive"))
      (node (ref "Q4") (pin "2") (pinfunction "S_2") (pintype "passive"))
      (node (ref "R12") (pin "1") (pinfunction "1_1") (pintype "passive"))
      (node (ref "R16") (pin "1") (pinfunction "1_1") (pintype "passive"))
      (node (ref "U1") (pin "3") (pinfunction "COM_3") (pintype "passive"))
      (node (ref "U2") (pin "3") (pinfunction "COM_3") (pintype "passive"))
      (node (ref "U5") (pin "5") (pinfunction "GND_5") (pintype "passive"))
      (node (ref "U6") (pin "2") (pinfunction "GND_2") (pintype "passive"))
      (node (ref "U7") (pin "2") (pinfunction "GND_2") (pintype "power_in"))
    )
    (net (code "46") (name "VCC") (class "Default")
      (node (ref "C18") (pin "2") (pintype "passive"))
      (node (ref "C5") (pin "1") (pinfunction "1_1") (pintype "passive"))
      (node (ref "C7") (pin "1") (pinfunction "1_1") (pintype "passive"))
      (node (ref "D5") (pin "A") (pinfunction "A_A") (pintype "passive"))
      (node (ref "D6") (pin "A") (pinfunction "A_A") (pintype "passive"))
      (node (ref "R22") (pin "2") (pinfunction "2_2") (pintype "passive"))
      (node (ref "U1") (pin "5") (pinfunction "VCC_5") (pintype "passive"))
      (node (ref "U2") (pin "5") (pinfunction "VCC_5") (pintype "passive"))
      (node (ref "U7") (pin "3") (pinfunction "IN_3") (pintype "input"))
    )
    (net (code "47") (name "unconnected-(U1-EN-Pad2)") (class "Default")
      (node (ref "U1") (pin "2") (pinfunction "EN_2") (pintype "passive"))
    )
    (net (code "48") (name "unconnected-(U2-EN-Pad2)") (class "Default")
      (node (ref "U2") (pin "2") (pinfunction "EN_2") (pintype "passive"))
    )
    (net (code "49") (name "unconnected-(U3-NRST-Pad7)") (class "Default")
      (node (ref "U3") (pin "7") (pinfunction "NRST_7") (pintype "input"))
    )
    (net (code "50") (name "unconnected-(U3-PA0_WKUP-Pad10)") (class "Default")
      (node (ref "U3") (pin "10") (pinfunction "PA0_WKUP_10") (pintype "bidirectional"))
    )
    (net (code "51") (name "unconnected-(U3-PA1-Pad11)") (class "Default")
      (node (ref "U3") (pin "11") (pinfunction "PA1_11") (pintype "bidirectional"))
    )
    (net (code "52") (name "unconnected-(U3-PA2-Pad12)") (class "Default")
      (node (ref "U3") (pin "12") (pinfunction "PA2_12") (pintype "bidirectional"))
    )
    (net (code "53") (name "unconnected-(U3-PA3-Pad13)") (class "Default")
      (node (ref "U3") (pin "13") (pinfunction "PA3_13") (pintype "bidirectional"))
    )
    (net (code "54") (name "unconnected-(U3-PA4-Pad14)") (class "Default")
      (node (ref "U3") (pin "14") (pinfunction "PA4_14") (pintype "bidirectional"))
    )
    (net (code "55") (name "unconnected-(U3-PA5-Pad15)") (class "Default")
      (node (ref "U3") (pin "15") (pinfunction "PA5_15") (pintype "bidirectional"))
    )
    (net (code "56") (name "unconnected-(U3-PA6-Pad16)") (class "Default")
      (node (ref "U3") (pin "16") (pinfunction "PA6_16") (pintype "bidirectional"))
    )
    (net (code "57") (name "unconnected-(U3-PA7-Pad17)") (class "Default")
      (node (ref "U3") (pin "17") (pinfunction "PA7_17") (pintype "bidirectional"))
    )
    (net (code "58") (name "unconnected-(U3-PA10-Pad31)") (class "Default")
      (node (ref "U3") (pin "31") (pinfunction "PA10_31") (pintype "bidirectional"))
    )
    (net (code "59") (name "unconnected-(U3-PA11-Pad32)") (class "Default")
      (node (ref "U3") (pin "32") (pinfunction "PA11_32") (pintype "bidirectional"))
    )
    (net (code "60") (name "unconnected-(U3-PA12-Pad33)") (class "Default")
      (node (ref "U3") (pin "33") (pinfunction "PA12_33") (pintype "bidirectional"))
    )
    (net (code "61") (name "unconnected-(U3-PA15-Pad38)") (class "Default")
      (node (ref "U3") (pin "38") (pinfunction "PA15_38") (pintype "bidirectional"))
    )
    (net (code "62") (name "unconnected-(U3-PB0-Pad18)") (class "Default")
      (node (ref "U3") (pin "18") (pinfunction "PB0_18") (pintype "bidirectional"))
    )
    (net (code "63") (name "unconnected-(U3-PB1-Pad19)") (class "Default")
      (node (ref "U3") (pin "19") (pinfunction "PB1_19") (pintype "bidirectional"))
    )
    (net (code "64") (name "unconnected-(U3-PB2-Pad20)") (class "Default")
      (node (ref "U3") (pin "20") (pinfunction "PB2_20") (pintype "bidirectional"))
    )
    (net (code "65") (name "unconnected-(U3-PB3-Pad39)") (class "Default")
      (node (ref "U3") (pin "39") (pinfunction "PB3_39") (pintype "bidirectional"))
    )
    (net (code "66") (name "unconnected-(U3-PB4-Pad40)") (class "Default")
      (node (ref "U3") (pin "40") (pinfunction "PB4_40") (pintype "bidirectional"))
    )
    (net (code "67") (name "unconnected-(U3-PB5-Pad41)") (class "Default")
      (node (ref "U3") (pin "41") (pinfunction "PB5_41") (pintype "bidirectional"))
    )
    (net (code "68") (name "unconnected-(U3-PB8-Pad45)") (class "Default")
      (node (ref "U3") (pin "45") (pinfunction "PB8_45") (pintype "bidirectional"))
    )
    (net (code "69") (name "unconnected-(U3-PB9-Pad46)") (class "Default")
      (node (ref "U3") (pin "46") (pinfunction "PB9_46") (pintype "bidirectional"))
    )
    (net (code "70") (name "unconnected-(U3-PB12-Pad25)") (class "Default")
      (node (ref "U3") (pin "25") (pinfunction "PB12_25") (pintype "bidirectional"))
    )
    (net (code "71") (name "unconnected-(U3-PB13-Pad26)") (class "Default")
      (node (ref "U3") (pin "26") (pinfunction "PB13_26") (pintype "bidirectional"))
    )
    (net (code "72") (name "unconnected-(U3-PB14-Pad27)") (class "Default")
      (node (ref "U3") (pin "27") (pinfunction "PB14_27") (pintype "bidirectional"))
    )
    (net (code "73") (name "unconnected-(U3-PB15-Pad28)") (class "Default")
      (node (ref "U3") (pin "28") (pinfunction "PB15_28") (pintype "bidirectional"))
    )
    (net (code "74") (name "unconnected-(U3-PC13-TAMPER-RTC-Pad2)") (class "Default")
      (node (ref "U3") (pin "2") (pinfunction "PC13-TAMPER-RTC_2") (pintype "bidirectional"))
    )
    (net (code "75") (name "unconnected-(U3-PC15-OSC32_OUT-Pad4)") (class "Default")
      (node (ref "U3") (pin "4") (pinfunction "PC15-OSC32_OUT_4") (pintype "bidirectional"))
    )
    (net (code "76") (name "unconnected-(U4-3Y-Pad6)") (class "Default")
      (node (ref "U4") (pin "6") (pinfunction "3Y_6") (pintype "output"))
    )
    (net (code "77") (name "unconnected-(U4-4Y-Pad8)") (class "Default")
      (node (ref "U4") (pin "8") (pinfunction "4Y_8") (pintype "output"))
    )
    (net (code "78") (name "unconnected-(U4-5A-Pad11)") (class "Default")
      (node (ref "U4") (pin "11") (pinfunction "5A_11") (pintype "input"))
    )
    (net (code "79") (name "unconnected-(U4-5Y-Pad10)") (class "Default")
      (node (ref "U4") (pin "10") (pinfunction "5Y_10") (pintype "output"))
    )
    (net (code "80") (name "unconnected-(U4-6A-Pad13)") (class "Default")
      (node (ref "U4") (pin "13") (pinfunction "6A_13") (pintype "input"))
    )
    (net (code "81") (name "unconnected-(U4-6Y-Pad12)") (class "Default")
      (node (ref "U4") (pin "12") (pinfunction "6Y_12") (pintype "output"))
    )
  )
)
